# oxygen_sensing.net
KiCad netlist of a schematic drawn in EAGLE
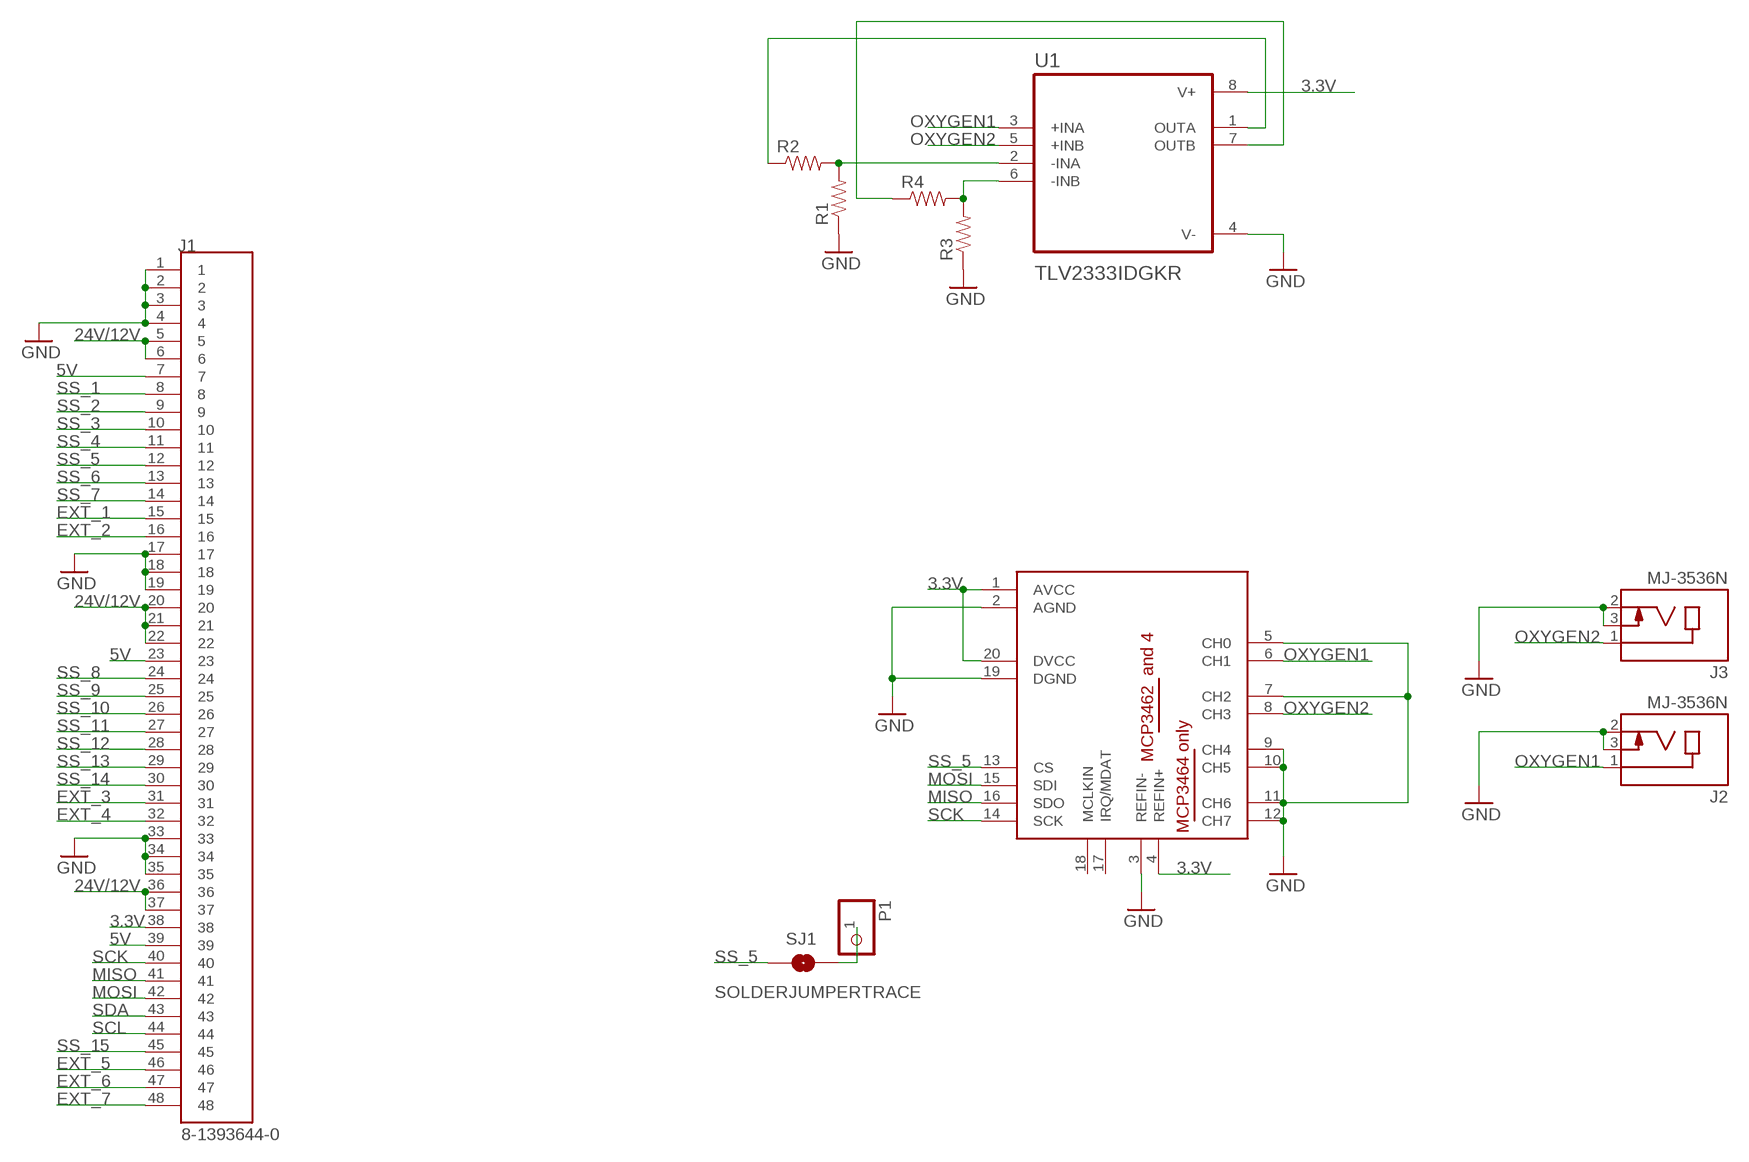
[diagram p0: schematic, sheet 1]

(export (version "E")
  (design (tool "Eeschema 10.0.6"))
  (components
    (comp (ref "J1")
      (value "8-1393644-0")
      (footprint "eagle-import:TE_8-1393644-0")
      (fields (field (name "MF") "TE Connectivity"))
      (libsource (lib "eagle-import") (part "8-1393644-0"))
    )
    (comp (ref "J2")
      (value "MJ-3536N")
      (footprint "eagle-import:CUI_MJ-3536N")
      (fields (field (name "MF") "CUI Devices"))
      (libsource (lib "eagle-import") (part "MJ-3536N"))
    )
    (comp (ref "J3")
      (value "MJ-3536N")
      (footprint "eagle-import:CUI_MJ-3536N")
      (fields (field (name "MF") "CUI Devices"))
      (libsource (lib "eagle-import") (part "MJ-3536N"))
    )
    (comp (ref "P1")
      (value "PINHD-1X1")
      (footprint "eagle-import:1X01")
      (libsource (lib "eagle-import") (part "PINHD-1X1"))
    )
    (comp (ref "R1")
      (value "RESISTOR0805-RES")
      (footprint "eagle-import:0805")
      (libsource (lib "eagle-import") (part "RESISTOR0805-RES"))
    )
    (comp (ref "R2")
      (value "RESISTOR0805-RES")
      (footprint "eagle-import:0805")
      (libsource (lib "eagle-import") (part "RESISTOR0805-RES"))
    )
    (comp (ref "R3")
      (value "RESISTOR0805-RES")
      (footprint "eagle-import:0805")
      (libsource (lib "eagle-import") (part "RESISTOR0805-RES"))
    )
    (comp (ref "R4")
      (value "RESISTOR0805-RES")
      (footprint "eagle-import:0805")
      (libsource (lib "eagle-import") (part "RESISTOR0805-RES"))
    )
    (comp (ref "SJ1")
      (value "SOLDERJUMPERTRACE")
      (footprint "eagle-import:SJ_2S-TRACE")
      (libsource (lib "eagle-import") (part "SOLDERJUMPERTRACE"))
    )
    (comp (ref "U$1")
      (value "MCP346X-E/ST")
      (footprint "eagle-import:TSSOP20")
      (libsource (lib "eagle-import") (part "MCP346X-E/ST"))
    )
    (comp (ref "U1")
      (value "TLV2333IDGKR")
      (footprint "eagle-import:SOP65P490X110-8N")
      (fields (field (name "MF") "Texas Instruments"))
      (libsource (lib "eagle-import") (part "TLV2333IDGKR"))
    )
  )
  (nets
    (net (code "1") (name "/3.3V") (class "Default")
      (node (ref "J1") (pin "38") (pinfunction "38_38") (pintype "passive"))
      (node (ref "U$1") (pin "1") (pinfunction "AVCC_1") (pintype "bidirectional"))
      (node (ref "U$1") (pin "20") (pinfunction "DVCC_20") (pintype "bidirectional"))
      (node (ref "U$1") (pin "4") (pinfunction "REFIN+_4") (pintype "bidirectional"))
      (node (ref "U1") (pin "8") (pinfunction "V+_8") (pintype "power_in"))
    )
    (net (code "2") (name "/5V") (class "Default")
      (node (ref "J1") (pin "23") (pinfunction "23_23") (pintype "passive"))
      (node (ref "J1") (pin "39") (pinfunction "39_39") (pintype "passive"))
      (node (ref "J1") (pin "7") (pinfunction "7_7") (pintype "passive"))
    )
    (net (code "3") (name "/24V{slash}12V") (class "Default")
      (node (ref "J1") (pin "20") (pinfunction "20_20") (pintype "passive"))
      (node (ref "J1") (pin "21") (pinfunction "21_21") (pintype "passive"))
      (node (ref "J1") (pin "22") (pinfunction "22_22") (pintype "passive"))
      (node (ref "J1") (pin "36") (pinfunction "36_36") (pintype "passive"))
      (node (ref "J1") (pin "37") (pinfunction "37_37") (pintype "passive"))
      (node (ref "J1") (pin "5") (pinfunction "5_5") (pintype "passive"))
      (node (ref "J1") (pin "6") (pinfunction "6_6") (pintype "passive"))
    )
    (net (code "4") (name "/EXT_1") (class "Default")
      (node (ref "J1") (pin "15") (pinfunction "15_15") (pintype "passive"))
    )
    (net (code "5") (name "/EXT_2") (class "Default")
      (node (ref "J1") (pin "16") (pinfunction "16_16") (pintype "passive"))
    )
    (net (code "6") (name "/EXT_3") (class "Default")
      (node (ref "J1") (pin "31") (pinfunction "31_31") (pintype "passive"))
    )
    (net (code "7") (name "/EXT_4") (class "Default")
      (node (ref "J1") (pin "32") (pinfunction "32_32") (pintype "passive"))
    )
    (net (code "8") (name "/EXT_5") (class "Default")
      (node (ref "J1") (pin "46") (pinfunction "46_46") (pintype "passive"))
    )
    (net (code "9") (name "/EXT_6") (class "Default")
      (node (ref "J1") (pin "47") (pinfunction "47_47") (pintype "passive"))
    )
    (net (code "10") (name "/EXT_7") (class "Default")
      (node (ref "J1") (pin "48") (pinfunction "48_48") (pintype "passive"))
    )
    (net (code "11") (name "/MISO") (class "Default")
      (node (ref "J1") (pin "41") (pinfunction "41_41") (pintype "passive"))
      (node (ref "U$1") (pin "16") (pinfunction "SDO_16") (pintype "bidirectional"))
    )
    (net (code "12") (name "/MOSI") (class "Default")
      (node (ref "J1") (pin "42") (pinfunction "42_42") (pintype "passive"))
      (node (ref "U$1") (pin "15") (pinfunction "SDI_15") (pintype "bidirectional"))
    )
    (net (code "13") (name "/OXYGEN1") (class "Default")
      (node (ref "J2") (pin "1") (pinfunction "1_1") (pintype "passive"))
      (node (ref "U$1") (pin "6") (pinfunction "CH1_6") (pintype "bidirectional"))
      (node (ref "U1") (pin "3") (pinfunction "+INA_3") (pintype "input"))
    )
    (net (code "14") (name "/OXYGEN2") (class "Default")
      (node (ref "J3") (pin "1") (pinfunction "1_1") (pintype "passive"))
      (node (ref "U$1") (pin "8") (pinfunction "CH3_8") (pintype "bidirectional"))
      (node (ref "U1") (pin "5") (pinfunction "+INB_5") (pintype "input"))
    )
    (net (code "15") (name "/SCK") (class "Default")
      (node (ref "J1") (pin "40") (pinfunction "40_40") (pintype "passive"))
      (node (ref "U$1") (pin "14") (pinfunction "SCK_14") (pintype "bidirectional"))
    )
    (net (code "16") (name "/SCL") (class "Default")
      (node (ref "J1") (pin "44") (pinfunction "44_44") (pintype "passive"))
    )
    (net (code "17") (name "/SDA") (class "Default")
      (node (ref "J1") (pin "43") (pinfunction "43_43") (pintype "passive"))
    )
    (net (code "18") (name "/SS_1") (class "Default")
      (node (ref "J1") (pin "8") (pinfunction "8_8") (pintype "passive"))
    )
    (net (code "19") (name "/SS_2") (class "Default")
      (node (ref "J1") (pin "9") (pinfunction "9_9") (pintype "passive"))
    )
    (net (code "20") (name "/SS_3") (class "Default")
      (node (ref "J1") (pin "10") (pinfunction "10_10") (pintype "passive"))
    )
    (net (code "21") (name "/SS_4") (class "Default")
      (node (ref "J1") (pin "11") (pinfunction "11_11") (pintype "passive"))
    )
    (net (code "22") (name "/SS_5") (class "Default")
      (node (ref "J1") (pin "12") (pinfunction "12_12") (pintype "passive"))
      (node (ref "SJ1") (pin "1") (pinfunction "1_1") (pintype "passive"))
      (node (ref "U$1") (pin "13") (pinfunction "CS_13") (pintype "bidirectional"))
    )
    (net (code "23") (name "/SS_6") (class "Default")
      (node (ref "J1") (pin "13") (pinfunction "13_13") (pintype "passive"))
    )
    (net (code "24") (name "/SS_7") (class "Default")
      (node (ref "J1") (pin "14") (pinfunction "14_14") (pintype "passive"))
    )
    (net (code "25") (name "/SS_8") (class "Default")
      (node (ref "J1") (pin "24") (pinfunction "24_24") (pintype "passive"))
    )
    (net (code "26") (name "/SS_9") (class "Default")
      (node (ref "J1") (pin "25") (pinfunction "25_25") (pintype "passive"))
    )
    (net (code "27") (name "/SS_10") (class "Default")
      (node (ref "J1") (pin "26") (pinfunction "26_26") (pintype "passive"))
    )
    (net (code "28") (name "/SS_11") (class "Default")
      (node (ref "J1") (pin "27") (pinfunction "27_27") (pintype "passive"))
    )
    (net (code "29") (name "/SS_12") (class "Default")
      (node (ref "J1") (pin "28") (pinfunction "28_28") (pintype "passive"))
    )
    (net (code "30") (name "/SS_13") (class "Default")
      (node (ref "J1") (pin "29") (pinfunction "29_29") (pintype "passive"))
    )
    (net (code "31") (name "/SS_14") (class "Default")
      (node (ref "J1") (pin "30") (pinfunction "30_30") (pintype "passive"))
    )
    (net (code "32") (name "/SS_15") (class "Default")
      (node (ref "J1") (pin "45") (pinfunction "45_45") (pintype "passive"))
    )
    (net (code "33") (name "GND") (class "Default")
      (node (ref "J1") (pin "1") (pinfunction "1_1") (pintype "passive"))
      (node (ref "J1") (pin "17") (pinfunction "17_17") (pintype "passive"))
      (node (ref "J1") (pin "18") (pinfunction "18_18") (pintype "passive"))
      (node (ref "J1") (pin "19") (pinfunction "19_19") (pintype "passive"))
      (node (ref "J1") (pin "2") (pinfunction "2_2") (pintype "passive"))
      (node (ref "J1") (pin "3") (pinfunction "3_3") (pintype "passive"))
      (node (ref "J1") (pin "33") (pinfunction "33_33") (pintype "passive"))
      (node (ref "J1") (pin "34") (pinfunction "34_34") (pintype "passive"))
      (node (ref "J1") (pin "35") (pinfunction "35_35") (pintype "passive"))
      (node (ref "J1") (pin "4") (pinfunction "4_4") (pintype "passive"))
      (node (ref "J2") (pin "2") (pinfunction "2_2") (pintype "passive"))
      (node (ref "J2") (pin "3") (pinfunction "3_3") (pintype "passive"))
      (node (ref "J3") (pin "2") (pinfunction "2_2") (pintype "passive"))
      (node (ref "J3") (pin "3") (pinfunction "3_3") (pintype "passive"))
      (node (ref "R1") (pin "1") (pinfunction "1_1") (pintype "passive"))
      (node (ref "R3") (pin "1") (pinfunction "1_1") (pintype "passive"))
      (node (ref "U$1") (pin "10") (pinfunction "CH5_10") (pintype "bidirectional"))
      (node (ref "U$1") (pin "11") (pinfunction "CH6_11") (pintype "bidirectional"))
      (node (ref "U$1") (pin "12") (pinfunction "CH7_12") (pintype "bidirectional"))
      (node (ref "U$1") (pin "19") (pinfunction "DGND_19") (pintype "bidirectional"))
      (node (ref "U$1") (pin "2") (pinfunction "AGND_2") (pintype "bidirectional"))
      (node (ref "U$1") (pin "3") (pinfunction "REFIN-_3") (pintype "bidirectional"))
      (node (ref "U$1") (pin "5") (pinfunction "CH0_5") (pintype "bidirectional"))
      (node (ref "U$1") (pin "7") (pinfunction "CH2_7") (pintype "bidirectional"))
      (node (ref "U$1") (pin "9") (pinfunction "CH4_9") (pintype "bidirectional"))
      (node (ref "U1") (pin "4") (pinfunction "V-_4") (pintype "power_in"))
    )
    (net (code "34") (name "Net-(P1-Pad1)") (class "Default")
      (node (ref "P1") (pin "1") (pinfunction "1_1") (pintype "passive"))
      (node (ref "SJ1") (pin "2") (pinfunction "2_2") (pintype "passive"))
    )
    (net (code "35") (name "Net-(U1--INA)") (class "Default")
      (node (ref "R1") (pin "2") (pinfunction "2_2") (pintype "passive"))
      (node (ref "R2") (pin "2") (pinfunction "2_2") (pintype "passive"))
      (node (ref "U1") (pin "2") (pinfunction "-INA_2") (pintype "input"))
    )
    (net (code "36") (name "Net-(U1--INB)") (class "Default")
      (node (ref "R3") (pin "2") (pinfunction "2_2") (pintype "passive"))
      (node (ref "R4") (pin "2") (pinfunction "2_2") (pintype "passive"))
      (node (ref "U1") (pin "6") (pinfunction "-INB_6") (pintype "input"))
    )
    (net (code "37") (name "Net-(U1-OUTA)") (class "Default")
      (node (ref "R2") (pin "1") (pinfunction "1_1") (pintype "passive"))
      (node (ref "U1") (pin "1") (pinfunction "OUTA_1") (pintype "output"))
    )
    (net (code "38") (name "Net-(U1-OUTB)") (class "Default")
      (node (ref "R4") (pin "1") (pinfunction "1_1") (pintype "passive"))
      (node (ref "U1") (pin "7") (pinfunction "OUTB_7") (pintype "output"))
    )
    (net (code "39") (name "unconnected-(U$1-IRQ{slash}MDAT-Pad17)") (class "Default")
      (node (ref "U$1") (pin "17") (pinfunction "IRQ/MDAT_17") (pintype "bidirectional"))
    )
    (net (code "40") (name "unconnected-(U$1-MCLKIN-Pad18)") (class "Default")
      (node (ref "U$1") (pin "18") (pinfunction "MCLKIN_18") (pintype "bidirectional"))
    )
  )
)
